# z80.net
KiCad netlist of a schematic drawn in Altium Designer
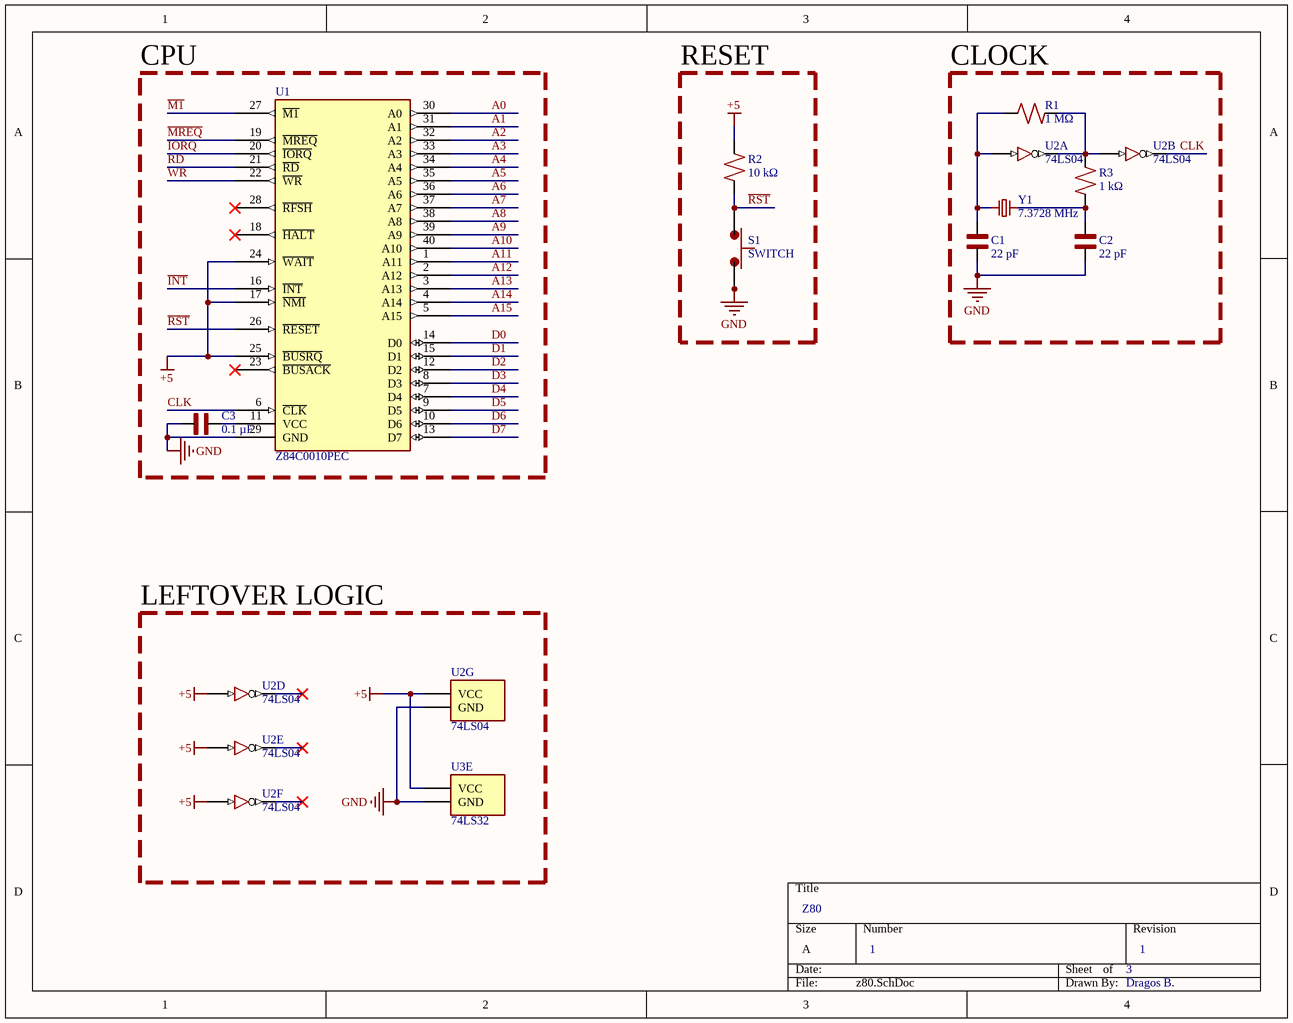
[diagram p0: z80.SchDoc]

(export (version "E")
  (design (tool "Eeschema 10.0.6"))
  (components
    (comp (ref "C1")
      (value "22 pF")
      (footprint "Capacitor")
      (fields (field (name "MP") "ECWFG70105K") (field (name "MF") "Panasonic"))
      (libsource (lib "components") (part "CAPACITOR"))
    )
    (comp (ref "C2")
      (value "22 pF")
      (footprint "Capacitor")
      (fields (field (name "MP") "ECWFG70105K") (field (name "MF") "Panasonic"))
      (libsource (lib "components") (part "CAPACITOR"))
    )
    (comp (ref "C3")
      (value "0.1 µF")
      (footprint "Capacitor")
      (fields (field (name "MP") "ECWFG70105K") (field (name "MF") "Panasonic"))
      (libsource (lib "") (part "CAPACITOR_1"))
    )
    (comp (ref "R1")
      (value "1 MΩ")
      (footprint "Axial 0.4")
      (fields (field (name "MP") "ERJU01J131C"))
      (libsource (lib "components") (part "RESISTOR"))
    )
    (comp (ref "R2")
      (value "10 kΩ")
      (footprint "Axial 0.4")
      (fields (field (name "MP") "ERJU01J131C"))
      (libsource (lib "components") (part "RESISTOR"))
    )
    (comp (ref "R3")
      (value "1 kΩ")
      (footprint "Axial 0.4")
      (fields (field (name "MP") "ERJU01J131C"))
      (libsource (lib "components") (part "RESISTOR"))
    )
    (comp (ref "S1")
      (value "SWITCH")
      (footprint "SW_PTS645SL43SMTR92LFS")
      (fields (field (name "MF") "ALPS") (field (name "MP") "SKRPABE010"))
      (libsource (lib "components") (part "SWITCH"))
    )
    (comp (ref "U1")
      (value "Z84C0010PEC")
      (footprint "DIP40")
      (libsource (lib "components") (part "Z84C0010PEC"))
    )
    (comp (ref "U2")
      (value "74LS04")
      (footprint "DIP14")
      (description "Hex Inverters")
      (libsource (lib "components") (part "74LS04"))
    )
    (comp (ref "U3") (value "74LS32") (footprint "DIP14") (libsource (lib "components") (part "74LS32")))
    (comp (ref "Y1")
      (value "7.3728 MHz")
      (footprint "HC49S")
      (fields (field (name "MF") "IQD Frequency Products") (field (name "MP") "LFXTAL003056B"))
      (libsource (lib "components") (part "CRYSTAL"))
    )
  )
  (nets
    (net (code "1") (name "+5") (class "Default")
      (node (ref "R2") (pin "2") (pinfunction "2_2") (pintype "passive"))
      (node (ref "U1") (pin "17") (pinfunction "NMI_17") (pintype "input"))
      (node (ref "U1") (pin "24") (pinfunction "WAIT_24") (pintype "input"))
      (node (ref "U1") (pin "25") (pinfunction "BUSRQ_25") (pintype "input"))
      (node (ref "U2") (pin "11") (pinfunction "A5_11") (pintype "input"))
      (node (ref "U2") (pin "13") (pinfunction "A6_13") (pintype "input"))
      (node (ref "U2") (pin "14") (pinfunction "VCC_14") (pintype "power_in"))
      (node (ref "U2") (pin "9") (pinfunction "A4_9") (pintype "input"))
      (node (ref "U3") (pin "14") (pinfunction "VCC_14") (pintype "power_in"))
    )
    (net (code "2") (name "/A0") (class "Default")
      (node (ref "U1") (pin "30") (pinfunction "A0_30") (pintype "output"))
    )
    (net (code "3") (name "/A1") (class "Default")
      (node (ref "U1") (pin "31") (pinfunction "A1_31") (pintype "output"))
    )
    (net (code "4") (name "/A2") (class "Default")
      (node (ref "U1") (pin "32") (pinfunction "A2_32") (pintype "output"))
    )
    (net (code "5") (name "/A3") (class "Default")
      (node (ref "U1") (pin "33") (pinfunction "A3_33") (pintype "output"))
    )
    (net (code "6") (name "/A4") (class "Default")
      (node (ref "U1") (pin "34") (pinfunction "A4_34") (pintype "output"))
    )
    (net (code "7") (name "/A5") (class "Default")
      (node (ref "U1") (pin "35") (pinfunction "A5_35") (pintype "output"))
    )
    (net (code "8") (name "/A6") (class "Default")
      (node (ref "U1") (pin "36") (pinfunction "A6_36") (pintype "output"))
    )
    (net (code "9") (name "/A7") (class "Default")
      (node (ref "U1") (pin "37") (pinfunction "A7_37") (pintype "output"))
    )
    (net (code "10") (name "/A8") (class "Default")
      (node (ref "U1") (pin "38") (pinfunction "A8_38") (pintype "output"))
    )
    (net (code "11") (name "/A9") (class "Default")
      (node (ref "U1") (pin "39") (pinfunction "A9_39") (pintype "output"))
    )
    (net (code "12") (name "/A10") (class "Default")
      (node (ref "U1") (pin "40") (pinfunction "A10_40") (pintype "output"))
    )
    (net (code "13") (name "/A11") (class "Default")
      (node (ref "U1") (pin "1") (pinfunction "A11_1") (pintype "output"))
    )
    (net (code "14") (name "/A12") (class "Default")
      (node (ref "U1") (pin "2") (pinfunction "A12_2") (pintype "output"))
    )
    (net (code "15") (name "/A13") (class "Default")
      (node (ref "U1") (pin "3") (pinfunction "A13_3") (pintype "output"))
    )
    (net (code "16") (name "/A14") (class "Default")
      (node (ref "U1") (pin "4") (pinfunction "A14_4") (pintype "output"))
    )
    (net (code "17") (name "/A15") (class "Default")
      (node (ref "U1") (pin "5") (pinfunction "A15_5") (pintype "output"))
    )
    (net (code "18") (name "/CLK") (class "Default")
      (node (ref "U1") (pin "6") (pinfunction "CLK_6") (pintype "input"))
      (node (ref "U2") (pin "4") (pinfunction "Y2_4") (pintype "output"))
    )
    (net (code "19") (name "/D0") (class "Default")
      (node (ref "U1") (pin "14") (pinfunction "D0_14") (pintype "bidirectional"))
    )
    (net (code "20") (name "/D1") (class "Default")
      (node (ref "U1") (pin "15") (pinfunction "D1_15") (pintype "bidirectional"))
    )
    (net (code "21") (name "/D2") (class "Default")
      (node (ref "U1") (pin "12") (pinfunction "D2_12") (pintype "bidirectional"))
    )
    (net (code "22") (name "/D3") (class "Default")
      (node (ref "U1") (pin "8") (pinfunction "D3_8") (pintype "bidirectional"))
    )
    (net (code "23") (name "/D4") (class "Default")
      (node (ref "U1") (pin "7") (pinfunction "D4_7") (pintype "bidirectional"))
    )
    (net (code "24") (name "/D5") (class "Default")
      (node (ref "U1") (pin "9") (pinfunction "D5_9") (pintype "bidirectional"))
    )
    (net (code "25") (name "/D6") (class "Default")
      (node (ref "U1") (pin "10") (pinfunction "D6_10") (pintype "bidirectional"))
    )
    (net (code "26") (name "/D7") (class "Default")
      (node (ref "U1") (pin "13") (pinfunction "D7_13") (pintype "bidirectional"))
    )
    (net (code "27") (name "/INT") (class "Default")
      (node (ref "U1") (pin "16") (pinfunction "INT_16") (pintype "input"))
    )
    (net (code "28") (name "/IORQ") (class "Default")
      (node (ref "U1") (pin "20") (pinfunction "IORQ_20") (pintype "output"))
    )
    (net (code "29") (name "/M1") (class "Default")
      (node (ref "U1") (pin "27") (pinfunction "M1_27") (pintype "output"))
    )
    (net (code "30") (name "/MREQ") (class "Default")
      (node (ref "U1") (pin "19") (pinfunction "MREQ_19") (pintype "output"))
    )
    (net (code "31") (name "/RD") (class "Default")
      (node (ref "U1") (pin "21") (pinfunction "RD_21") (pintype "output"))
    )
    (net (code "32") (name "/RST") (class "Default")
      (node (ref "R2") (pin "1") (pinfunction "1_1") (pintype "passive"))
      (node (ref "S1") (pin "1") (pinfunction "1_1") (pintype "passive"))
      (node (ref "S1") (pin "2") (pinfunction "1_2") (pintype "passive"))
      (node (ref "U1") (pin "26") (pinfunction "RESET_26") (pintype "input"))
    )
    (net (code "33") (name "/WR") (class "Default")
      (node (ref "U1") (pin "22") (pinfunction "WR_22") (pintype "output"))
    )
    (net (code "34") (name "GND") (class "Default")
      (node (ref "C1") (pin "1") (pinfunction "1_1") (pintype "passive"))
      (node (ref "C2") (pin "1") (pinfunction "1_1") (pintype "passive"))
      (node (ref "C3") (pin "2") (pinfunction "2_2") (pintype "passive"))
      (node (ref "S1") (pin "3") (pinfunction "2_3") (pintype "passive"))
      (node (ref "S1") (pin "4") (pinfunction "2_4") (pintype "passive"))
      (node (ref "U1") (pin "29") (pinfunction "GND_29") (pintype "power_in"))
      (node (ref "U2") (pin "7") (pinfunction "GND_7") (pintype "power_in"))
      (node (ref "U3") (pin "7") (pinfunction "GND_7") (pintype "power_in"))
    )
    (net (code "35") (name "Net-(C2-Pad2)") (class "Default")
      (node (ref "C2") (pin "2") (pinfunction "2_2") (pintype "passive"))
      (node (ref "R3") (pin "1") (pinfunction "1_1") (pintype "passive"))
      (node (ref "Y1") (pin "2") (pinfunction "2_2") (pintype "passive"))
    )
    (net (code "36") (name "Net-(U1-VCC)") (class "Default")
      (node (ref "C3") (pin "1") (pinfunction "1_1") (pintype "passive"))
      (node (ref "U1") (pin "11") (pinfunction "VCC_11") (pintype "power_in"))
    )
    (net (code "37") (name "Net-(U2A-A1)") (class "Default")
      (node (ref "C1") (pin "2") (pinfunction "2_2") (pintype "passive"))
      (node (ref "R1") (pin "2") (pinfunction "2_2") (pintype "passive"))
      (node (ref "U2") (pin "1") (pinfunction "A1_1") (pintype "input"))
      (node (ref "Y1") (pin "1") (pinfunction "1_1") (pintype "passive"))
    )
    (net (code "38") (name "Net-(U2A-A2)") (class "Default")
      (node (ref "R1") (pin "1") (pinfunction "1_1") (pintype "passive"))
      (node (ref "R3") (pin "2") (pinfunction "2_2") (pintype "passive"))
      (node (ref "U2") (pin "2") (pinfunction "A2_2") (pintype "output"))
      (node (ref "U2") (pin "3") (pinfunction "A2_3") (pintype "input"))
    )
    (net (code "39") (name "unconnected-(U1-BUSACK-Pad23)") (class "Default")
      (node (ref "U1") (pin "23") (pinfunction "BUSACK_23") (pintype "output+no_connect"))
    )
    (net (code "40") (name "unconnected-(U1-HALT-Pad18)") (class "Default")
      (node (ref "U1") (pin "18") (pinfunction "HALT_18") (pintype "output+no_connect"))
    )
    (net (code "41") (name "unconnected-(U1-RFSH-Pad28)") (class "Default")
      (node (ref "U1") (pin "28") (pinfunction "RFSH_28") (pintype "output+no_connect"))
    )
    (net (code "42") (name "unconnected-(U2D-Y4-Pad8)") (class "Default")
      (node (ref "U2") (pin "8") (pinfunction "Y4_8") (pintype "output+no_connect"))
    )
    (net (code "43") (name "unconnected-(U2E-Y5-Pad10)") (class "Default")
      (node (ref "U2") (pin "10") (pinfunction "Y5_10") (pintype "output+no_connect"))
    )
    (net (code "44") (name "unconnected-(U2F-Y6-Pad12)") (class "Default")
      (node (ref "U2") (pin "12") (pinfunction "Y6_12") (pintype "output+no_connect"))
    )
  )
)
